# SparkFun_GPS_RTK_Surveyor.net
KiCad netlist of a schematic drawn in EAGLE
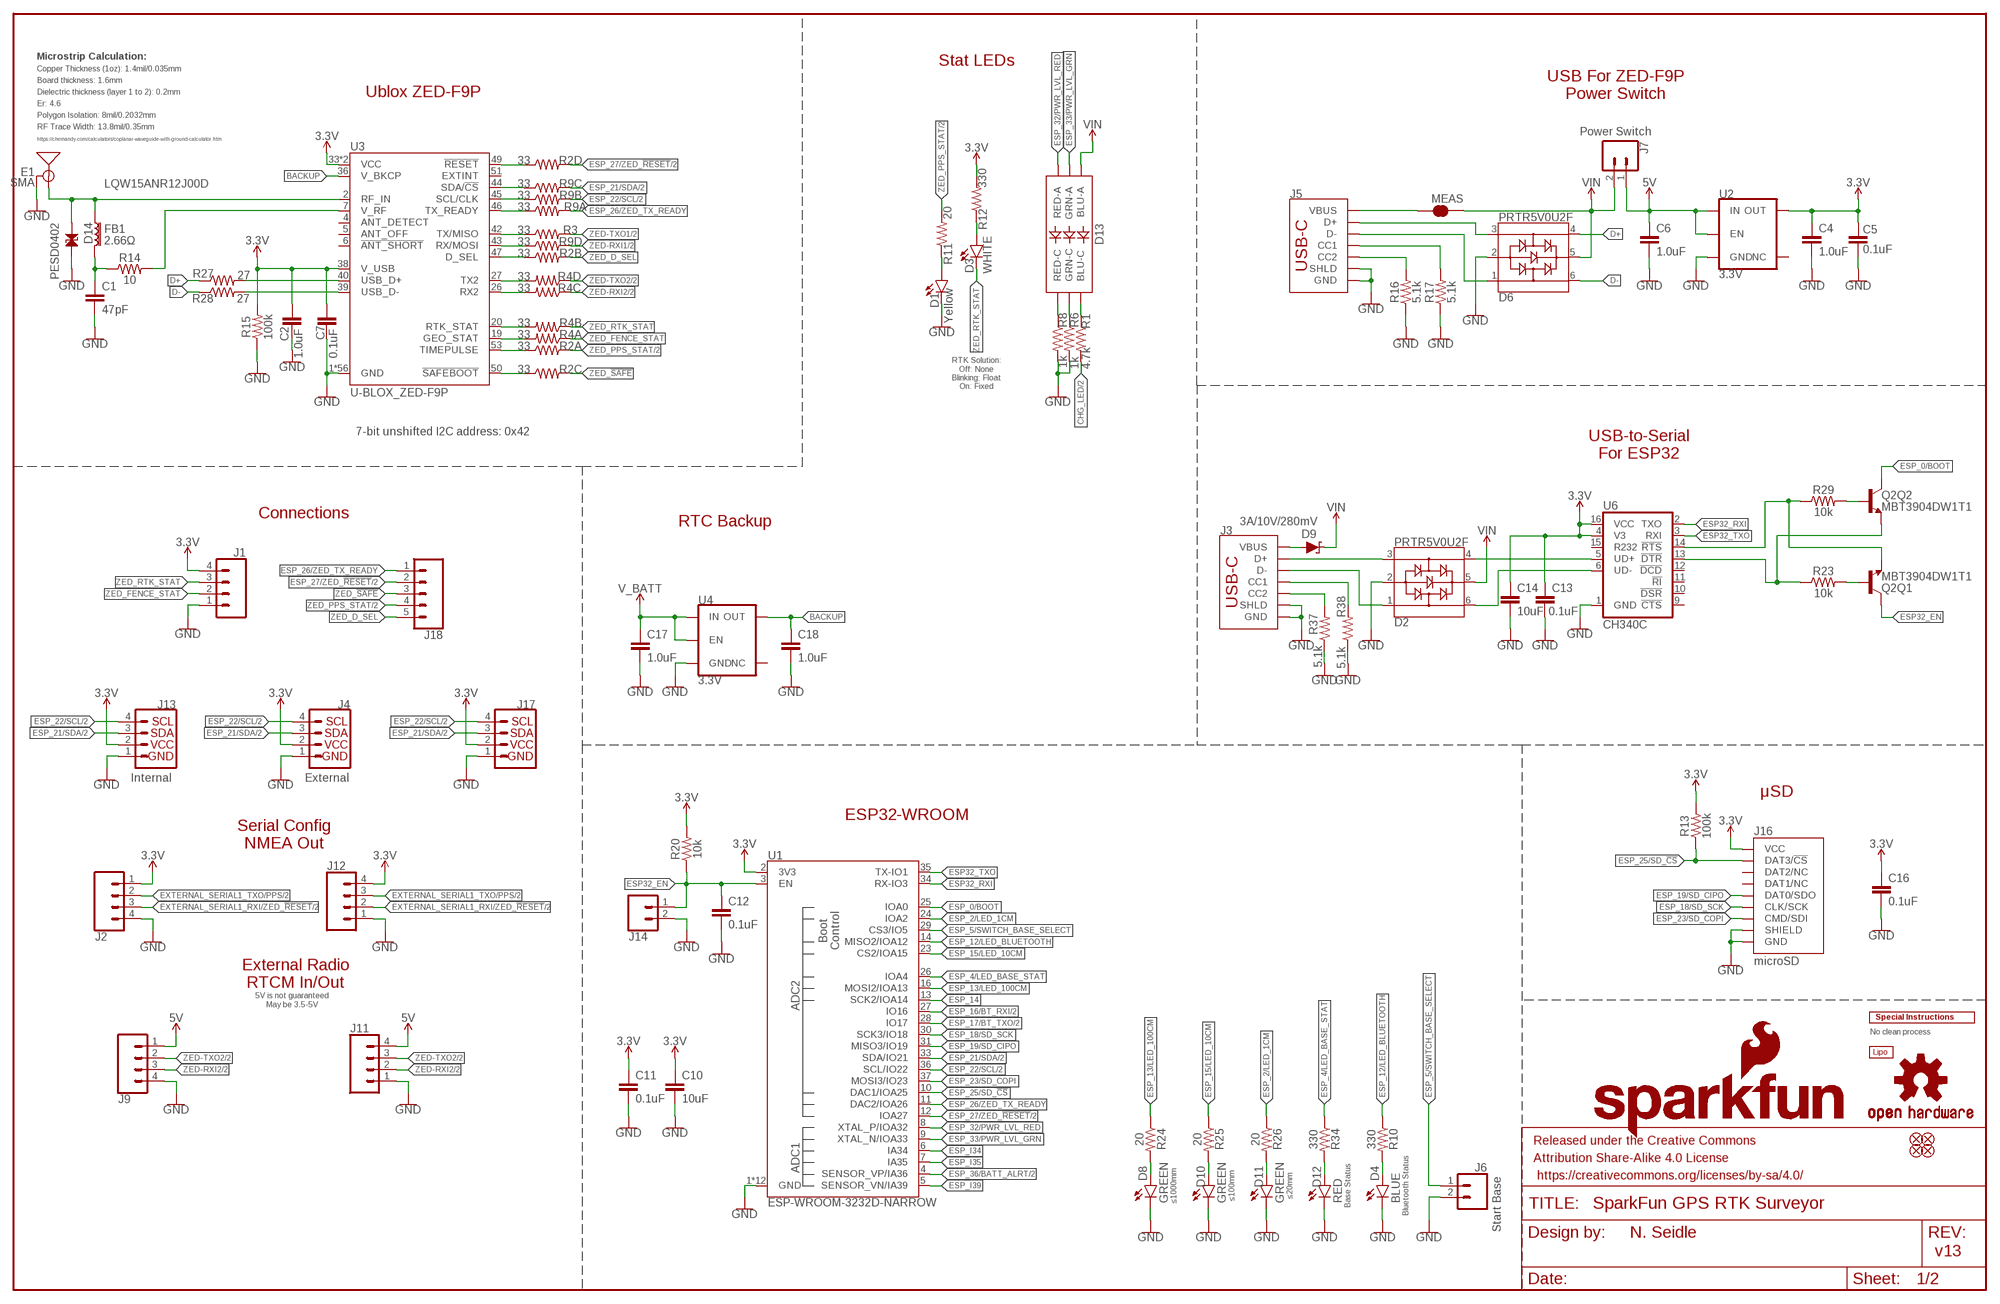
[diagram p0: schematic, sheet 1]
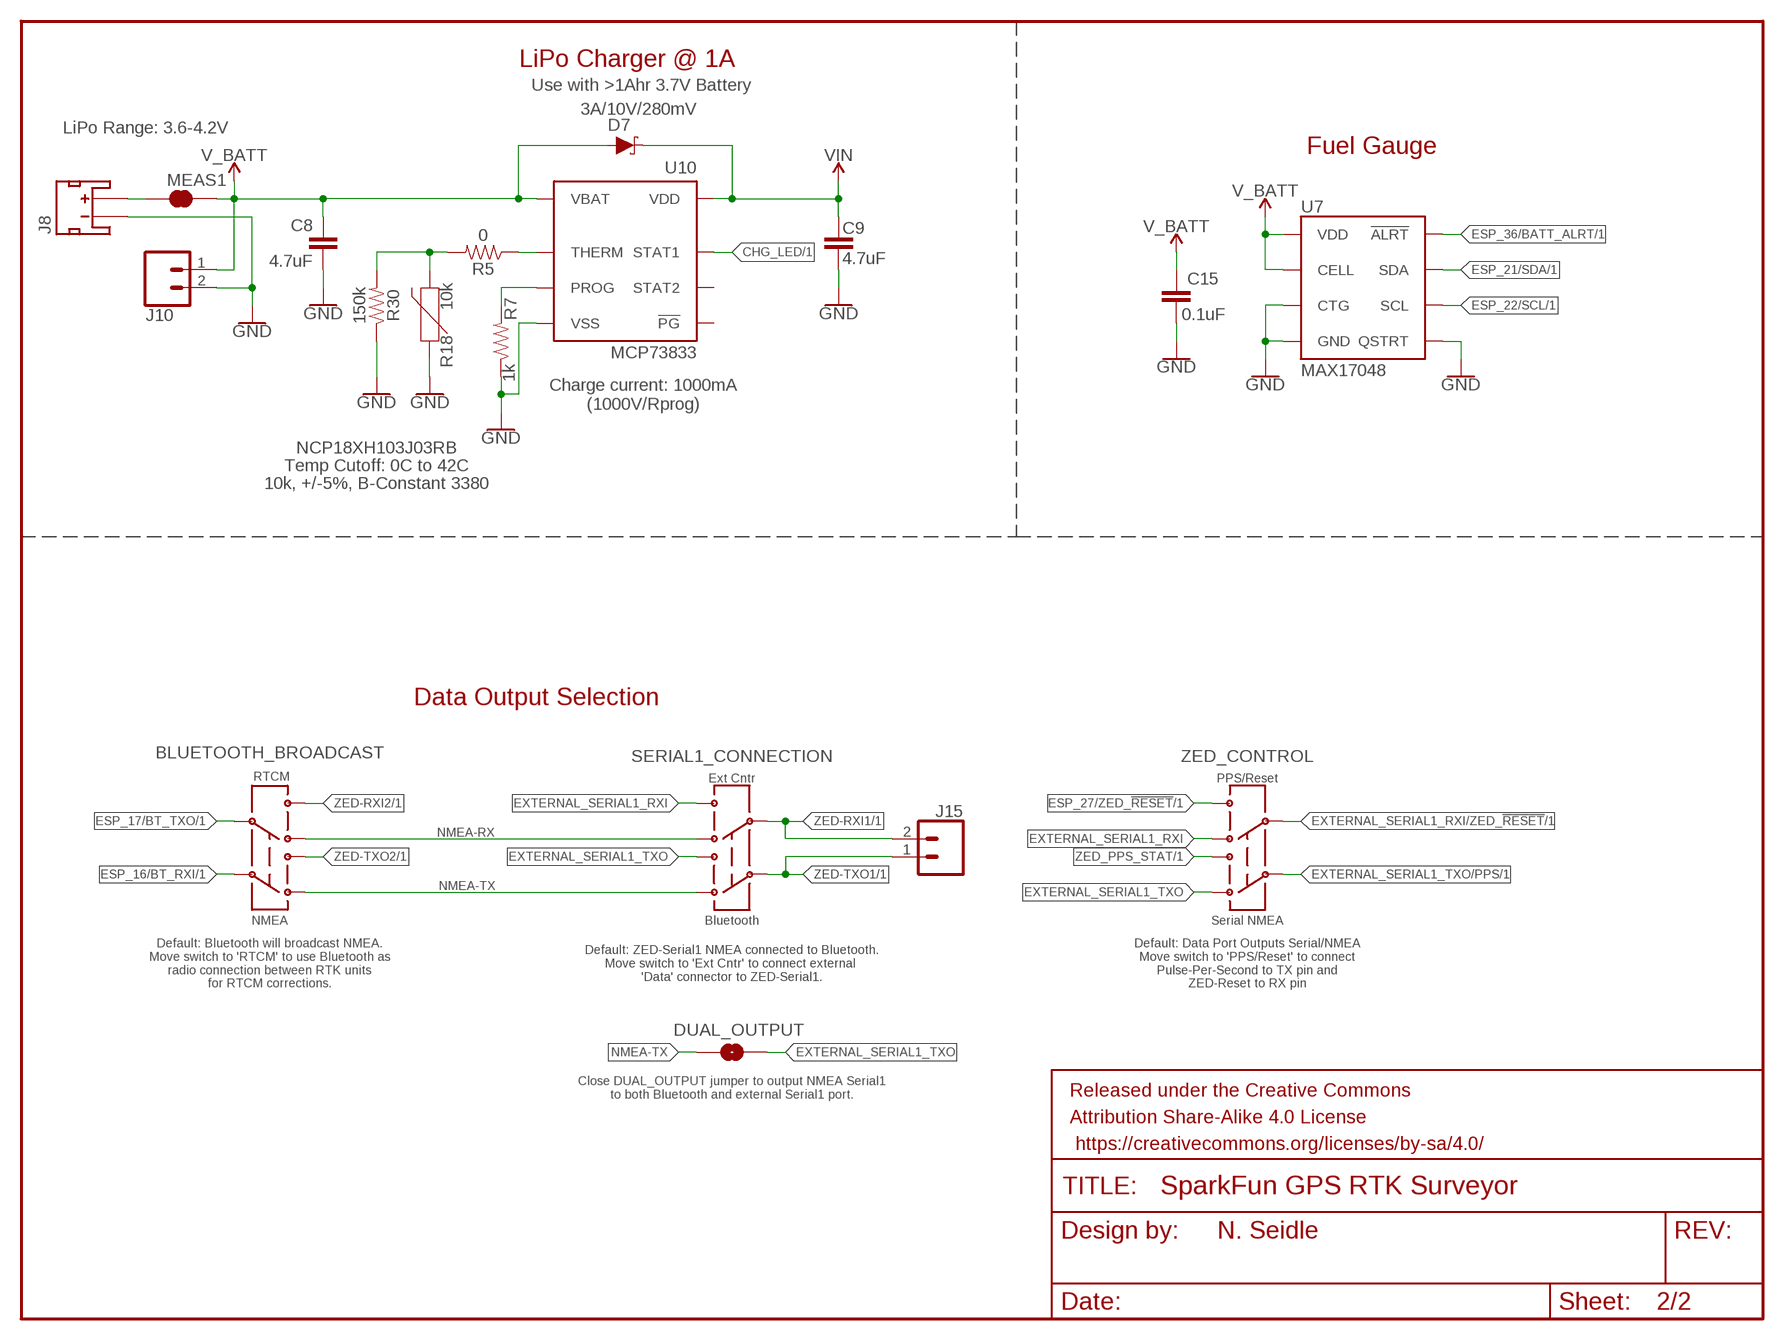
[diagram p1: schematic, sheet 2]

(export (version "E")
  (design (tool "Eeschema 10.0.6"))
  (components
    (comp (ref "BT1")
      (value "LIPO-OUTLINE1000")
      (footprint "eagle-import:LIPO-1000")
      (libsource (lib "eagle-import") (part "LIPO-OUTLINE1000"))
    )
    (comp (ref "C1")
      (value "47pF")
      (footprint "eagle-import:0402")
      (libsource (lib "eagle-import") (part "47PF-0402-25V-5%-X7R"))
    )
    (comp (ref "C2")
      (value "1.0uF")
      (footprint "eagle-import:0603")
      (libsource (lib "eagle-import") (part "1.0UF-0603-16V-10%-X7R"))
    )
    (comp (ref "C4")
      (value "1.0uF")
      (footprint "eagle-import:0603")
      (libsource (lib "eagle-import") (part "1.0UF-0603-16V-10%-X7R"))
    )
    (comp (ref "C5")
      (value "0.1uF")
      (footprint "eagle-import:0603")
      (libsource (lib "eagle-import") (part "0.1UF-0603-25V-5%"))
    )
    (comp (ref "C6")
      (value "1.0uF")
      (footprint "eagle-import:0603")
      (libsource (lib "eagle-import") (part "1.0UF-0603-16V-10%-X7R"))
    )
    (comp (ref "C7")
      (value "0.1uF")
      (footprint "eagle-import:0603")
      (libsource (lib "eagle-import") (part "0.1UF-0603-25V-5%"))
    )
    (comp (ref "C10")
      (value "10uF")
      (footprint "eagle-import:0603")
      (libsource (lib "eagle-import") (part "10UF-0603-6.3V-20%"))
    )
    (comp (ref "C11")
      (value "0.1uF")
      (footprint "eagle-import:0603")
      (libsource (lib "eagle-import") (part "0.1UF-0603-25V-(+80/-20%)"))
    )
    (comp (ref "C12")
      (value "0.1uF")
      (footprint "eagle-import:0603")
      (libsource (lib "eagle-import") (part "0.1UF-0603-25V-(+80/-20%)"))
    )
    (comp (ref "C13")
      (value "0.1uF")
      (footprint "eagle-import:0603")
      (libsource (lib "eagle-import") (part "0.1UF-0603-25V-(+80/-20%)"))
    )
    (comp (ref "C14")
      (value "10uF")
      (footprint "eagle-import:0603")
      (libsource (lib "eagle-import") (part "10UF-0603-6.3V-20%"))
    )
    (comp (ref "C16")
      (value "0.1uF")
      (footprint "eagle-import:0603")
      (libsource (lib "eagle-import") (part "0.1UF-0603-25V-(+80/-20%)"))
    )
    (comp (ref "C17")
      (value "1.0uF")
      (footprint "eagle-import:0603")
      (libsource (lib "eagle-import") (part "1.0UF-0603-16V-10%-X7R"))
    )
    (comp (ref "C18")
      (value "1.0uF")
      (footprint "eagle-import:0603")
      (libsource (lib "eagle-import") (part "1.0UF-0603-16V-10%-X7R"))
    )
    (comp (ref "D1")
      (value "Yellow")
      (footprint "eagle-import:LED-0603")
      (libsource (lib "eagle-import") (part "LED-YELLOW0603"))
    )
    (comp (ref "D2")
      (value "PRTR5V0U2F")
      (footprint "eagle-import:SOT886")
      (libsource (lib "eagle-import") (part "PRTR5V0U2F"))
    )
    (comp (ref "D3")
      (value "WHITE")
      (footprint "eagle-import:LED-0603")
      (libsource (lib "eagle-import") (part "LED-WHITE0603"))
    )
    (comp (ref "D4")
      (value "BLUE")
      (footprint "eagle-import:LED-0603")
      (libsource (lib "eagle-import") (part "LED-BLUE0603"))
    )
    (comp (ref "D6")
      (value "PRTR5V0U2F")
      (footprint "eagle-import:SOT886")
      (libsource (lib "eagle-import") (part "PRTR5V0U2F"))
    )
    (comp (ref "D8")
      (value "GREEN")
      (footprint "eagle-import:LED-0603")
      (libsource (lib "eagle-import") (part "LED-GREEN0603"))
    )
    (comp (ref "D9")
      (value "3A/10V/280mV")
      (footprint "eagle-import:SOD-323")
      (libsource (lib "eagle-import") (part "DIODE-SCHOTTKY-BAT60A"))
    )
    (comp (ref "D10")
      (value "GREEN")
      (footprint "eagle-import:LED-0603")
      (libsource (lib "eagle-import") (part "LED-GREEN0603"))
    )
    (comp (ref "D11")
      (value "GREEN")
      (footprint "eagle-import:LED-0603")
      (libsource (lib "eagle-import") (part "LED-GREEN0603"))
    )
    (comp (ref "D12")
      (value "RED")
      (footprint "eagle-import:LED-0603")
      (libsource (lib "eagle-import") (part "LED-RED0603"))
    )
    (comp (ref "D13")
      (value "LED-RGBBRG")
      (footprint "eagle-import:LED-TRICOLOR-5050")
      (libsource (lib "eagle-import") (part "LED-RGBBRG"))
    )
    (comp (ref "D14")
      (value "PESD0402")
      (footprint "eagle-import:0402")
      (fields
        (field (name "DIGIKEY_PART") "PESD0402-140CT-ND")
        (field (name "MOUSE_PART") "650-PESD0402-140")
      )
      (libsource (lib "eagle-import") (part "PESD0402"))
    )
    (comp (ref "E1")
      (value "SMA")
      (footprint "eagle-import:SMA-EDGE-SMD")
      (libsource (lib "eagle-import") (part "ANTENNA-SMA-GROUNDEDEDGE_SMA_SMD"))
    )
    (comp (ref "FB1")
      (value "2.66Ω")
      (footprint "eagle-import:0402-TIGHT")
      (libsource (lib "eagle-import") (part "FERRITE_BEAD-0402-2.66Ω-1GHZ"))
    )
    (comp (ref "FRAME2")
      (value "FRAME-LEDGER")
      (footprint "eagle-import:CREATIVE_COMMONS")
      (libsource (lib "eagle-import") (part "FRAME-LEDGER"))
    )
    (comp (ref "J1")
      (value "CONN_041X04_NO_SILK_NO_POP")
      (footprint "eagle-import:1X04_NO_SILK")
      (libsource (lib "eagle-import") (part "CONN_041X04_NO_SILK_NO_POP"))
    )
    (comp (ref "J2")
      (value "CONN_04JST-SMD-LOCKING")
      (footprint "eagle-import:JST-4-SMD-1.25MM-LOCKING")
      (libsource (lib "eagle-import") (part "CONN_04JST-SMD-LOCKING"))
    )
    (comp (ref "J3")
      (value "USB Female Type C Connector")
      (footprint "eagle-import:USB-C-16P_4LAYER-PADS")
      (libsource (lib "eagle-import") (part "USB_C_4-LAYER_PADS"))
    )
    (comp (ref "J4")
      (value "External")
      (footprint "eagle-import:JST04_1MM_RA")
      (libsource (lib "eagle-import") (part "I2C_STANDARDQWIIC"))
    )
    (comp (ref "J5")
      (value "USB Female Type C Connector")
      (footprint "eagle-import:USB-C-16P_4LAYER-PADS")
      (libsource (lib "eagle-import") (part "USB_C_4-LAYER_PADS"))
    )
    (comp (ref "J6")
      (value "Start Base")
      (footprint "eagle-import:JST-2-SMD")
      (libsource (lib "eagle-import") (part "CONN_02-JST-2MM-SMT"))
    )
    (comp (ref "J7")
      (value "Power Switch")
      (footprint "eagle-import:JST-2-SMD")
      (libsource (lib "eagle-import") (part "CONN_02-JST-2MM-SMT"))
    )
    (comp (ref "J9")
      (value "CONN_04JST-SMD-LOCKING")
      (footprint "eagle-import:JST-4-SMD-1.25MM-LOCKING")
      (libsource (lib "eagle-import") (part "CONN_04JST-SMD-LOCKING"))
    )
    (comp (ref "J11")
      (value "CONN_041X04_NO_SILK_NO_POP")
      (footprint "eagle-import:1X04_NO_SILK")
      (libsource (lib "eagle-import") (part "CONN_041X04_NO_SILK_NO_POP"))
    )
    (comp (ref "J12")
      (value "CONN_041X04_NO_SILK_NO_POP")
      (footprint "eagle-import:1X04_NO_SILK")
      (libsource (lib "eagle-import") (part "CONN_041X04_NO_SILK_NO_POP"))
    )
    (comp (ref "J13")
      (value "Internal")
      (footprint "eagle-import:JST04_1MM_RA")
      (libsource (lib "eagle-import") (part "I2C_STANDARDQWIIC"))
    )
    (comp (ref "J14")
      (value "CONN_021X02_NO_SILK")
      (footprint "eagle-import:1X02_NO_SILK")
      (libsource (lib "eagle-import") (part "CONN_021X02_NO_SILK"))
    )
    (comp (ref "J16")
      (value "microSD")
      (footprint "eagle-import:MICRO-SD-SOCKET")
      (libsource (lib "eagle-import") (part "MICRO-SD-SDIOPUSH-PUSH"))
    )
    (comp (ref "J17")
      (value "Qwiic Right Angle")
      (footprint "eagle-import:1X04_NO_SILK")
      (libsource (lib "eagle-import") (part "I2C_STANDARD_NO_SILK"))
    )
    (comp (ref "J18")
      (value "CONN_05NO_SILK")
      (footprint "eagle-import:1X05_NO_SILK")
      (libsource (lib "eagle-import") (part "CONN_05NO_SILK"))
    )
    (comp (ref "JP21")
      (value "FIDUCIALUFIDUCIAL")
      (footprint "eagle-import:FIDUCIAL-MICRO")
      (libsource (lib "eagle-import") (part "FIDUCIALUFIDUCIAL"))
    )
    (comp (ref "JP61")
      (value "FIDUCIALUFIDUCIAL")
      (footprint "eagle-import:FIDUCIAL-MICRO")
      (libsource (lib "eagle-import") (part "FIDUCIALUFIDUCIAL"))
    )
    (comp (ref "JP71")
      (value "FIDUCIALUFIDUCIAL")
      (footprint "eagle-import:FIDUCIAL-MICRO")
      (libsource (lib "eagle-import") (part "FIDUCIALUFIDUCIAL"))
    )
    (comp (ref "JP81")
      (value "FIDUCIALUFIDUCIAL")
      (footprint "eagle-import:FIDUCIAL-MICRO")
      (libsource (lib "eagle-import") (part "FIDUCIALUFIDUCIAL"))
    )
    (comp (ref "LOGO1")
      (value "OSHW-LOGOMINI")
      (footprint "eagle-import:OSHW-LOGO-MINI")
      (libsource (lib "eagle-import") (part "OSHW-LOGOMINI"))
    )
    (comp (ref "LOGO2")
      (value "SFE_LOGO_NAME_FLAME.1_INCH")
      (footprint "eagle-import:SFE_LOGO_NAME_FLAME_.1")
      (libsource (lib "eagle-import") (part "SFE_LOGO_NAME_FLAME.1_INCH"))
    )
    (comp (ref "MEAS")
      (value "JUMPER-COMBO_2_NC_TRACE")
      (footprint "eagle-import:COMBO-JUMPER_2_NC_TRACE")
      (libsource (lib "eagle-import") (part "JUMPER-COMBO_2_NC_TRACE"))
    )
    (comp (ref "Q2")
      (value "MBT3904DW1T1")
      (footprint "eagle-import:SC70-6")
      (libsource (lib "eagle-import") (part "TRANS_NPN_DUAL-MBT3904DW1T1"))
    )
    (comp (ref "R1")
      (value "4.7k")
      (footprint "eagle-import:0603")
      (libsource (lib "eagle-import") (part "4.7KOHM-0603-1/10W-1%"))
    )
    (comp (ref "R2")
      (value "33")
      (footprint "eagle-import:1206_RA")
      (libsource (lib "eagle-import") (part "33OHM_RA-1206-1/16W-5%"))
    )
    (comp (ref "R3")
      (value "33")
      (footprint "eagle-import:0603")
      (libsource (lib "eagle-import") (part "33OHM-0603-1/10W-1%"))
    )
    (comp (ref "R4")
      (value "33")
      (footprint "eagle-import:1206_RA")
      (libsource (lib "eagle-import") (part "33OHM_RA-1206-1/16W-5%"))
    )
    (comp (ref "R6")
      (value "1k")
      (footprint "eagle-import:0603")
      (libsource (lib "eagle-import") (part "1KOHM-0603-1/10W-1%"))
    )
    (comp (ref "R8")
      (value "1k")
      (footprint "eagle-import:0603")
      (libsource (lib "eagle-import") (part "1KOHM-0603-1/10W-1%"))
    )
    (comp (ref "R9")
      (value "33")
      (footprint "eagle-import:1206_RA")
      (libsource (lib "eagle-import") (part "33OHM_RA-1206-1/16W-5%"))
    )
    (comp (ref "R10")
      (value "330")
      (footprint "eagle-import:0603")
      (libsource (lib "eagle-import") (part "330OHM-0603-1/10W-1%"))
    )
    (comp (ref "R11")
      (value "20")
      (footprint "eagle-import:0603")
      (libsource (lib "eagle-import") (part "20OHM-0603-1/10W-1%"))
    )
    (comp (ref "R12")
      (value "330")
      (footprint "eagle-import:0603")
      (libsource (lib "eagle-import") (part "330OHM-0603-1/10W-1%"))
    )
    (comp (ref "R13")
      (value "100k")
      (footprint "eagle-import:0603")
      (libsource (lib "eagle-import") (part "100KOHM-0603-1/10W-1%"))
    )
    (comp (ref "R14")
      (value "10")
      (footprint "eagle-import:0603")
      (libsource (lib "eagle-import") (part "10OHM-0603-1/10W-1%"))
    )
    (comp (ref "R15")
      (value "100k")
      (footprint "eagle-import:0603")
      (libsource (lib "eagle-import") (part "100KOHM-0603-1/10W-1%"))
    )
    (comp (ref "R16")
      (value "5.1k")
      (footprint "eagle-import:0603")
      (libsource (lib "eagle-import") (part "5.1KOHM5.1KOHM-0603-1/10W-1%"))
    )
    (comp (ref "R17")
      (value "5.1k")
      (footprint "eagle-import:0603")
      (libsource (lib "eagle-import") (part "5.1KOHM5.1KOHM-0603-1/10W-1%"))
    )
    (comp (ref "R20")
      (value "10k")
      (footprint "eagle-import:0603")
      (libsource (lib "eagle-import") (part "10KOHM-0603-1/10W-1%"))
    )
    (comp (ref "R23")
      (value "10k")
      (footprint "eagle-import:0603")
      (libsource (lib "eagle-import") (part "10KOHM-0603-1/10W-1%"))
    )
    (comp (ref "R24")
      (value "20")
      (footprint "eagle-import:0603")
      (libsource (lib "eagle-import") (part "20OHM-0603-1/10W-1%"))
    )
    (comp (ref "R25")
      (value "20")
      (footprint "eagle-import:0603")
      (libsource (lib "eagle-import") (part "20OHM-0603-1/10W-1%"))
    )
    (comp (ref "R26")
      (value "20")
      (footprint "eagle-import:0603")
      (libsource (lib "eagle-import") (part "20OHM-0603-1/10W-1%"))
    )
    (comp (ref "R27")
      (value "27")
      (footprint "eagle-import:0603")
      (libsource (lib "eagle-import") (part "27OHM-0603-1/10W-1%"))
    )
    (comp (ref "R28")
      (value "27")
      (footprint "eagle-import:0603")
      (libsource (lib "eagle-import") (part "27OHM-0603-1/10W-1%"))
    )
    (comp (ref "R29")
      (value "10k")
      (footprint "eagle-import:0603")
      (libsource (lib "eagle-import") (part "10KOHM-0603-1/10W-1%"))
    )
    (comp (ref "R34")
      (value "330")
      (footprint "eagle-import:0603")
      (libsource (lib "eagle-import") (part "330OHM-0603-1/10W-1%"))
    )
    (comp (ref "R37")
      (value "5.1k")
      (footprint "eagle-import:0603")
      (libsource (lib "eagle-import") (part "5.1KOHM5.1KOHM-0603-1/10W-1%"))
    )
    (comp (ref "R38")
      (value "5.1k")
      (footprint "eagle-import:0603")
      (libsource (lib "eagle-import") (part "5.1KOHM5.1KOHM-0603-1/10W-1%"))
    )
    (comp (ref "U$2")
      (value "SPECIAL_INSTRUCTIONS-ORDERING")
      (footprint "eagle-import:ORDERING_INSTRUCTIONS")
      (libsource (lib "eagle-import") (part "SPECIAL_INSTRUCTIONS-ORDERING"))
    )
    (comp (ref "U1")
      (value "ESP-WROOM-3232D-NARROW")
      (footprint "eagle-import:ESP-WROOM-32D-NARROW")
      (libsource (lib "eagle-import") (part "ESP-WROOM-3232D-NARROW"))
    )
    (comp (ref "U2")
      (value "3.3V")
      (footprint "eagle-import:SOT23-5")
      (libsource (lib "eagle-import") (part "V_REG_AP2112K-3.3V"))
    )
    (comp (ref "U3")
      (value "U-BLOX_ZED-F9P")
      (footprint "eagle-import:ZED-F9P")
      (libsource (lib "eagle-import") (part "U-BLOX_ZED-F9P"))
    )
    (comp (ref "U4")
      (value "3.3V")
      (footprint "eagle-import:SOT23-5")
      (libsource (lib "eagle-import") (part "V_REG_AP2112K-3.3V"))
    )
    (comp (ref "U6")
      (value "CH340C")
      (footprint "eagle-import:SO016")
      (libsource (lib "eagle-import") (part "CH340C"))
    )
    (comp (ref "BLUETOOTH_BROADCAST")
      (value "SWITCH-DPDT-SMD-AYZ0202")
      (footprint "eagle-import:SWITCH_DPDT_SMD_AYZ0202")
      (libsource (lib "eagle-import") (part "SWITCH-DPDT-SMD-AYZ0202"))
    )
    (comp (ref "C8")
      (value "4.7uF")
      (footprint "eagle-import:0603")
      (libsource (lib "eagle-import") (part "4.7UF-0603-35V-(20%)"))
    )
    (comp (ref "C9")
      (value "4.7uF")
      (footprint "eagle-import:0603")
      (libsource (lib "eagle-import") (part "4.7UF-0603-35V-(20%)"))
    )
    (comp (ref "C15")
      (value "0.1uF")
      (footprint "eagle-import:0603")
      (libsource (lib "eagle-import") (part "0.1UF-0603-25V-(+80/-20%)"))
    )
    (comp (ref "D7")
      (value "3A/10V/280mV")
      (footprint "eagle-import:SOD-323")
      (libsource (lib "eagle-import") (part "DIODE-SCHOTTKY-BAT60A"))
    )
    (comp (ref "DUAL_OUTPUT")
      (value "JUMPER-SMT_2_NO_SILK")
      (footprint "eagle-import:SMT-JUMPER_2_NO_SILK")
      (libsource (lib "eagle-import") (part "JUMPER-SMT_2_NO_SILK"))
    )
    (comp (ref "FRAME1")
      (value "FRAME-LETTERNO_PACKAGE")
      (footprint "eagle-import:DUMMY")
      (fields (field (name "DESIGNER") "Nobody"))
      (libsource (lib "eagle-import") (part "FRAME-LETTERNO_PACKAGE"))
    )
    (comp (ref "J8")
      (value "JST_2MM_MALE")
      (footprint "eagle-import:JST-2-SMD")
      (libsource (lib "eagle-import") (part "JST_2MM_MALE"))
    )
    (comp (ref "J10")
      (value "CONN_021X02_NO_SILK")
      (footprint "eagle-import:1X02_NO_SILK")
      (libsource (lib "eagle-import") (part "CONN_021X02_NO_SILK"))
    )
    (comp (ref "J15")
      (value "CONN_021X02_NO_SILK")
      (footprint "eagle-import:1X02_NO_SILK")
      (libsource (lib "eagle-import") (part "CONN_021X02_NO_SILK"))
    )
    (comp (ref "MEAS1")
      (value "JUMPER-COMBO_2_NC_TRACE")
      (footprint "eagle-import:COMBO-JUMPER_2_NC_TRACE")
      (libsource (lib "eagle-import") (part "JUMPER-COMBO_2_NC_TRACE"))
    )
    (comp (ref "R5")
      (value "0")
      (footprint "eagle-import:0603")
      (libsource (lib "eagle-import") (part "0OHM-0603-1/10W"))
    )
    (comp (ref "R7")
      (value "1k")
      (footprint "eagle-import:0603")
      (libsource (lib "eagle-import") (part "1KOHM-0603-1/10W-1%"))
    )
    (comp (ref "R18")
      (value "10k")
      (footprint "eagle-import:0603")
      (libsource (lib "eagle-import") (part "NTC-THERMISTOR-0603"))
    )
    (comp (ref "R30")
      (value "150k")
      (footprint "eagle-import:0603")
      (libsource (lib "eagle-import") (part "150KOHM-0603-1/10W-1%"))
    )
    (comp (ref "SERIAL1_CONNECTION")
      (value "SWITCH-DPDT-SMD-AYZ0202")
      (footprint "eagle-import:SWITCH_DPDT_SMD_AYZ0202")
      (libsource (lib "eagle-import") (part "SWITCH-DPDT-SMD-AYZ0202"))
    )
    (comp (ref "U7")
      (value "MAX17048")
      (footprint "eagle-import:DFN-8")
      (libsource (lib "eagle-import") (part "MAX17048DFN8"))
    )
    (comp (ref "U10")
      (value "MCP73833")
      (footprint "eagle-import:DFN-10")
      (libsource (lib "eagle-import") (part "MCP73833"))
    )
    (comp (ref "ZED_CONTROL")
      (value "SWITCH-DPDT-SMD-AYZ0202")
      (footprint "eagle-import:SWITCH_DPDT_SMD_AYZ0202")
      (libsource (lib "eagle-import") (part "SWITCH-DPDT-SMD-AYZ0202"))
    )
  )
  (nets
    (net (code "1") (name "3.3V") (class "Default")
      (node (ref "C10") (pin "1") (pinfunction "1_1") (pintype "passive"))
      (node (ref "C11") (pin "1") (pinfunction "1_1") (pintype "passive"))
      (node (ref "C13") (pin "1") (pinfunction "1_1") (pintype "passive"))
      (node (ref "C14") (pin "1") (pinfunction "1_1") (pintype "passive"))
      (node (ref "C16") (pin "1") (pinfunction "1_1") (pintype "passive"))
      (node (ref "C2") (pin "1") (pinfunction "1_1") (pintype "passive"))
      (node (ref "C4") (pin "1") (pinfunction "1_1") (pintype "passive"))
      (node (ref "C5") (pin "2") (pinfunction "2_2") (pintype "passive"))
      (node (ref "C7") (pin "2") (pinfunction "2_2") (pintype "passive"))
      (node (ref "J1") (pin "4") (pinfunction "4_4") (pintype "passive"))
      (node (ref "J12") (pin "4") (pinfunction "4_4") (pintype "passive"))
      (node (ref "J13") (pin "2") (pinfunction "2_2") (pintype "power_in"))
      (node (ref "J16") (pin "VCC") (pinfunction "VCC_VCC") (pintype "bidirectional"))
      (node (ref "J17") (pin "2") (pinfunction "2_2") (pintype "power_in"))
      (node (ref "J2") (pin "1") (pinfunction "1_1") (pintype "passive"))
      (node (ref "J4") (pin "2") (pinfunction "2_2") (pintype "power_in"))
      (node (ref "R12") (pin "2") (pinfunction "2_2") (pintype "passive"))
      (node (ref "R13") (pin "2") (pinfunction "2_2") (pintype "passive"))
      (node (ref "R15") (pin "2") (pinfunction "2_2") (pintype "passive"))
      (node (ref "R20") (pin "2") (pinfunction "2_2") (pintype "passive"))
      (node (ref "U1") (pin "2") (pinfunction "3V3_2") (pintype "bidirectional"))
      (node (ref "U2") (pin "5") (pinfunction "OUT_5") (pintype "passive"))
      (node (ref "U3") (pin "33") (pinfunction "VCC_33") (pintype "bidirectional"))
      (node (ref "U3") (pin "34") (pinfunction "VCC_34") (pintype "bidirectional"))
      (node (ref "U3") (pin "38") (pinfunction "V_USB_38") (pintype "bidirectional"))
      (node (ref "U6") (pin "16") (pinfunction "VCC_16") (pintype "bidirectional"))
      (node (ref "U6") (pin "4") (pinfunction "V3_4") (pintype "bidirectional"))
    )
    (net (code "2") (name "5V") (class "Default")
      (node (ref "C6") (pin "1") (pinfunction "1_1") (pintype "passive"))
      (node (ref "J11") (pin "4") (pinfunction "4_4") (pintype "passive"))
      (node (ref "J7") (pin "1") (pinfunction "2_1") (pintype "passive"))
      (node (ref "J9") (pin "1") (pinfunction "1_1") (pintype "passive"))
      (node (ref "U2") (pin "1") (pinfunction "IN_1") (pintype "input"))
      (node (ref "U2") (pin "3") (pinfunction "EN_3") (pintype "input"))
    )
    (net (code "3") (name "BACKUP") (class "Default")
      (node (ref "C18") (pin "1") (pinfunction "1_1") (pintype "passive"))
      (node (ref "U3") (pin "36") (pinfunction "V_BKCP_36") (pintype "bidirectional"))
      (node (ref "U4") (pin "5") (pinfunction "OUT_5") (pintype "passive"))
    )
    (net (code "4") (name "CHG_LED") (class "Default")
      (node (ref "R1") (pin "2") (pinfunction "2_2") (pintype "passive"))
      (node (ref "U10") (pin "3") (pinfunction "STAT1_3") (pintype "bidirectional"))
    )
    (net (code "5") (name "D+") (class "Default")
      (node (ref "D6") (pin "4") (pinfunction "4_4") (pintype "bidirectional"))
      (node (ref "R27") (pin "1") (pinfunction "1_1") (pintype "passive"))
    )
    (net (code "6") (name "D-") (class "Default")
      (node (ref "D6") (pin "6") (pinfunction "6_6") (pintype "bidirectional"))
      (node (ref "R28") (pin "1") (pinfunction "1_1") (pintype "passive"))
    )
    (net (code "7") (name "ESP32_EN") (class "Default")
      (node (ref "C12") (pin "1") (pinfunction "1_1") (pintype "passive"))
      (node (ref "J14") (pin "1") (pinfunction "1_1") (pintype "passive"))
      (node (ref "Q2") (pin "3") (pinfunction "C_3") (pintype "passive"))
      (node (ref "R20") (pin "1") (pinfunction "1_1") (pintype "passive"))
      (node (ref "U1") (pin "3") (pinfunction "EN_3") (pintype "bidirectional"))
    )
    (net (code "8") (name "ESP32_RXI") (class "Default")
      (node (ref "U1") (pin "34") (pinfunction "RX-IO3_34") (pintype "bidirectional"))
      (node (ref "U6") (pin "2") (pinfunction "TXO_2") (pintype "bidirectional"))
    )
    (net (code "9") (name "ESP32_TXO") (class "Default")
      (node (ref "U1") (pin "35") (pinfunction "TX-IO1_35") (pintype "bidirectional"))
      (node (ref "U6") (pin "3") (pinfunction "RXI_3") (pintype "bidirectional"))
    )
    (net (code "10") (name "ESP_0{slash}BOOT") (class "Default")
      (node (ref "Q2") (pin "6") (pinfunction "C_6") (pintype "passive"))
      (node (ref "U1") (pin "25") (pinfunction "IOA0_25") (pintype "bidirectional"))
    )
    (net (code "11") (name "ESP_2{slash}LED_1CM") (class "Default")
      (node (ref "R26") (pin "1") (pinfunction "1_1") (pintype "passive"))
      (node (ref "U1") (pin "24") (pinfunction "IOA2_24") (pintype "bidirectional"))
    )
    (net (code "12") (name "ESP_4{slash}LED_BASE_STAT") (class "Default")
      (node (ref "R34") (pin "1") (pinfunction "1_1") (pintype "passive"))
      (node (ref "U1") (pin "26") (pinfunction "IOA4_26") (pintype "bidirectional"))
    )
    (net (code "13") (name "ESP_5{slash}SWITCH_BASE_SELECT") (class "Default")
      (node (ref "J6") (pin "1") (pinfunction "2_1") (pintype "passive"))
      (node (ref "U1") (pin "29") (pinfunction "CS3/IO5_29") (pintype "bidirectional"))
    )
    (net (code "14") (name "ESP_12{slash}LED_BLUETOOTH") (class "Default")
      (node (ref "R10") (pin "1") (pinfunction "1_1") (pintype "passive"))
      (node (ref "U1") (pin "14") (pinfunction "MISO2/IOA12_14") (pintype "bidirectional"))
    )
    (net (code "15") (name "ESP_13{slash}LED_100CM") (class "Default")
      (node (ref "R24") (pin "1") (pinfunction "1_1") (pintype "passive"))
      (node (ref "U1") (pin "16") (pinfunction "MOSI2/IOA13_16") (pintype "bidirectional"))
    )
    (net (code "16") (name "ESP_14") (class "Default")
      (node (ref "U1") (pin "13") (pinfunction "SCK2/IOA14_13") (pintype "bidirectional"))
    )
    (net (code "17") (name "ESP_15{slash}LED_10CM") (class "Default")
      (node (ref "R25") (pin "1") (pinfunction "1_1") (pintype "passive"))
      (node (ref "U1") (pin "23") (pinfunction "CS2/IOA15_23") (pintype "bidirectional"))
    )
    (net (code "18") (name "ESP_16{slash}BT_RXI") (class "Default")
      (node (ref "BLUETOOTH_BROADCAST") (pin "2") (pinfunction "2_2") (pintype "bidirectional"))
      (node (ref "U1") (pin "27") (pinfunction "IO16_27") (pintype "bidirectional"))
    )
    (net (code "19") (name "ESP_17{slash}BT_TXO") (class "Default")
      (node (ref "BLUETOOTH_BROADCAST") (pin "5") (pinfunction "5_5") (pintype "bidirectional"))
      (node (ref "U1") (pin "28") (pinfunction "IO17_28") (pintype "bidirectional"))
    )
    (net (code "20") (name "ESP_18{slash}SD_SCK") (class "Default")
      (node (ref "J16") (pin "SCLK") (pinfunction "CLK/SCK_SCLK") (pintype "bidirectional"))
      (node (ref "U1") (pin "30") (pinfunction "SCK3/IO18_30") (pintype "bidirectional"))
    )
    (net (code "21") (name "ESP_19{slash}SD_CIPO") (class "Default")
      (node (ref "J16") (pin "DO/DAT0") (pinfunction "DAT0/SDO_DO/DAT0") (pintype "bidirectional"))
      (node (ref "U1") (pin "31") (pinfunction "MISO3/IO19_31") (pintype "bidirectional"))
    )
    (net (code "22") (name "ESP_21{slash}SDA") (class "Default")
      (node (ref "J13") (pin "3") (pinfunction "3_3") (pintype "passive"))
      (node (ref "J17") (pin "3") (pinfunction "3_3") (pintype "passive"))
      (node (ref "J4") (pin "3") (pinfunction "3_3") (pintype "passive"))
      (node (ref "R9") (pin "P6") (pinfunction "2_P6") (pintype "passive"))
      (node (ref "U1") (pin "33") (pinfunction "SDA/IO21_33") (pintype "bidirectional"))
      (node (ref "U7") (pin "8") (pinfunction "SDA_8") (pintype "input"))
    )
    (net (code "23") (name "ESP_22{slash}SCL") (class "Default")
      (node (ref "J13") (pin "4") (pinfunction "4_4") (pintype "passive"))
      (node (ref "J17") (pin "4") (pinfunction "4_4") (pintype "passive"))
      (node (ref "J4") (pin "4") (pinfunction "4_4") (pintype "passive"))
      (node (ref "R9") (pin "P7") (pinfunction "2_P7") (pintype "passive"))
      (node (ref "U1") (pin "36") (pinfunction "SCL/IO22_36") (pintype "bidirectional"))
      (node (ref "U7") (pin "7") (pinfunction "SCL_7") (pintype "output"))
    )
    (net (code "24") (name "ESP_23{slash}SD_COPI") (class "Default")
      (node (ref "J16") (pin "DI/CMD") (pinfunction "CMD/SDI_DI/CMD") (pintype "bidirectional"))
      (node (ref "U1") (pin "37") (pinfunction "MOSI3/IO23_37") (pintype "bidirectional"))
    )
    (net (code "25") (name "ESP_25{slash}SD_~{CS}") (class "Default")
      (node (ref "J16") (pin "CS/DAT3") (pinfunction "DAT3/~{CS}_CS/DAT3") (pintype "bidirectional"))
      (node (ref "R13") (pin "1") (pinfunction "1_1") (pintype "passive"))
      (node (ref "U1") (pin "10") (pinfunction "DAC1/IOA25_10") (pintype "bidirectional"))
    )
    (net (code "26") (name "ESP_26{slash}ZED_TX_READY") (class "Default")
      (node (ref "J18") (pin "1") (pinfunction "1_1") (pintype "passive"))
      (node (ref "R9") (pin "P8") (pinfunction "2_P8") (pintype "passive"))
      (node (ref "U1") (pin "11") (pinfunction "DAC2/IOA26_11") (pintype "bidirectional"))
    )
    (net (code "27") (name "ESP_27{slash}ZED_~{RESET}") (class "Default")
      (node (ref "J18") (pin "2") (pinfunction "2_2") (pintype "passive"))
      (node (ref "R2") (pin "P5") (pinfunction "2_P5") (pintype "passive"))
      (node (ref "U1") (pin "12") (pinfunction "IOA27_12") (pintype "bidirectional"))
      (node (ref "ZED_CONTROL") (pin "4") (pinfunction "4_4") (pintype "bidirectional"))
    )
    (net (code "28") (name "ESP_32{slash}PWR_LVL_RED") (class "Default")
      (node (ref "D13") (pin "5") (pinfunction "RED-A_5") (pintype "bidirectional"))
      (node (ref "U1") (pin "8") (pinfunction "XTAL_P/IOA32_8") (pintype "bidirectional"))
    )
    (net (code "29") (name "ESP_33{slash}PWR_LVL_GRN") (class "Default")
      (node (ref "D13") (pin "4") (pinfunction "GRN-A_4") (pintype "bidirectional"))
      (node (ref "U1") (pin "9") (pinfunction "XTAL_N/IOA33_9") (pintype "bidirectional"))
    )
    (net (code "30") (name "ESP_36{slash}BATT_ALRT") (class "Default")
      (node (ref "U1") (pin "4") (pinfunction "SENSOR_VP/IA36_4") (pintype "bidirectional"))
      (node (ref "U7") (pin "5") (pinfunction "~{ALRT}_5") (pintype "bidirectional"))
    )
    (net (code "31") (name "ESP_I34") (class "Default")
      (node (ref "U1") (pin "6") (pinfunction "IA34_6") (pintype "bidirectional"))
    )
    (net (code "32") (name "ESP_I35") (class "Default")
      (node (ref "U1") (pin "7") (pinfunction "IA35_7") (pintype "bidirectional"))
    )
    (net (code "33") (name "ESP_I39") (class "Default")
      (node (ref "U1") (pin "5") (pinfunction "SENSOR_VN/IA39_5") (pintype "bidirectional"))
    )
    (net (code "34") (name "EXTERNAL_SERIAL1_RXI") (class "Default")
      (node (ref "SERIAL1_CONNECTION") (pin "4") (pinfunction "4_4") (pintype "bidirectional"))
      (node (ref "ZED_CONTROL") (pin "6") (pinfunction "6_6") (pintype "bidirectional"))
    )
    (net (code "35") (name "EXTERNAL_SERIAL1_RXI{slash}ZED_~{RESET}") (class "Default")
      (node (ref "J12") (pin "2") (pinfunction "2_2") (pintype "passive"))
      (node (ref "J2") (pin "3") (pinfunction "3_3") (pintype "passive"))
      (node (ref "ZED_CONTROL") (pin "5") (pinfunction "5_5") (pintype "bidirectional"))
    )
    (net (code "36") (name "EXTERNAL_SERIAL1_TXO") (class "Default")
      (node (ref "DUAL_OUTPUT") (pin "2") (pinfunction "2_2") (pintype "passive"))
      (node (ref "SERIAL1_CONNECTION") (pin "1") (pinfunction "1_1") (pintype "bidirectional"))
      (node (ref "ZED_CONTROL") (pin "3") (pinfunction "3_3") (pintype "bidirectional"))
    )
    (net (code "37") (name "EXTERNAL_SERIAL1_TXO{slash}PPS") (class "Default")
      (node (ref "J12") (pin "3") (pinfunction "3_3") (pintype "passive"))
      (node (ref "J2") (pin "2") (pinfunction "2_2") (pintype "passive"))
      (node (ref "ZED_CONTROL") (pin "2") (pinfunction "2_2") (pintype "bidirectional"))
    )
    (net (code "38") (name "GND") (class "Default")
      (node (ref "C1") (pin "2") (pinfunction "2_2") (pintype "passive"))
      (node (ref "C10") (pin "2") (pinfunction "2_2") (pintype "passive"))
      (node (ref "C11") (pin "2") (pinfunction "2_2") (pintype "passive"))
      (node (ref "C12") (pin "2") (pinfunction "2_2") (pintype "passive"))
      (node (ref "C13") (pin "2") (pinfunction "2_2") (pintype "passive"))
      (node (ref "C14") (pin "2") (pinfunction "2_2") (pintype "passive"))
      (node (ref "C15") (pin "2") (pinfunction "2_2") (pintype "passive"))
      (node (ref "C16") (pin "2") (pinfunction "2_2") (pintype "passive"))
      (node (ref "C17") (pin "2") (pinfunction "2_2") (pintype "passive"))
      (node (ref "C18") (pin "2") (pinfunction "2_2") (pintype "passive"))
      (node (ref "C2") (pin "2") (pinfunction "2_2") (pintype "passive"))
      (node (ref "C4") (pin "2") (pinfunction "2_2") (pintype "passive"))
      (node (ref "C5") (pin "1") (pinfunction "1_1") (pintype "passive"))
      (node (ref "C6") (pin "2") (pinfunction "2_2") (pintype "passive"))
      (node (ref "C7") (pin "1") (pinfunction "1_1") (pintype "passive"))
      (node (ref "C8") (pin "2") (pinfunction "2_2") (pintype "passive"))
      (node (ref "C9") (pin "2") (pinfunction "2_2") (pintype "passive"))
      (node (ref "D1") (pin "C") (pinfunction "C_C") (pintype "passive"))
      (node (ref "D10") (pin "C") (pinfunction "C_C") (pintype "passive"))
      (node (ref "D11") (pin "C") (pinfunction "C_C") (pintype "passive"))
      (node (ref "D12") (pin "C") (pinfunction "C_C") (pintype "passive"))
      (node (ref "D14") (pin "2") (pinfunction "2_2") (pintype "bidirectional"))
      (node (ref "D2") (pin "2") (pinfunction "2_2") (pintype "power_in"))
      (node (ref "D4") (pin "C") (pinfunction "C_C") (pintype "passive"))
      (node (ref "D6") (pin "2") (pinfunction "2_2") (pintype "power_in"))
      (node (ref "D8") (pin "C") (pinfunction "C_C") (pintype "passive"))
      (node (ref "E1") (pin "GND@0") (pinfunction "GND_GND@0") (pintype "bidirectional"))
      (node (ref "E1") (pin "GND@1") (pinfunction "GND_GND@1") (pintype "bidirectional"))
      (node (ref "J1") (pin "1") (pinfunction "1_1") (pintype "passive"))
      (node (ref "J10") (pin "2") (pinfunction "2_2") (pintype "passive"))
      (node (ref "J11") (pin "1") (pinfunction "1_1") (pintype "passive"))
      (node (ref "J12") (pin "1") (pinfunction "1_1") (pintype "passive"))
      (node (ref "J13") (pin "1") (pinfunction "1_1") (pintype "power_in"))
      (node (ref "J14") (pin "2") (pinfunction "2_2") (pintype "passive"))
      (node (ref "J16") (pin "CD1") (pinfunction "SHIELD_CD1") (pintype "bidirectional"))
      (node (ref "J16") (pin "GND") (pinfunction "GND_GND") (pintype "bidirectional"))
      (node (ref "J16") (pin "GND1") (pinfunction "GND_GND1") (pintype "bidirectional"))
      (node (ref "J16") (pin "GND3") (pinfunction "GND_GND3") (pintype "bidirectional"))
      (node (ref "J17") (pin "1") (pinfunction "1_1") (pintype "power_in"))
      (node (ref "J2") (pin "4") (pinfunction "4_4") (pintype "passive"))
      (node (ref "J3") (pin "GND") (pinfunction "GND_GND") (pintype "bidirectional"))
      (node (ref "J3") (pin "GND2") (pinfunction "GND_GND2") (pintype "bidirectional"))
      (node (ref "J3") (pin "SHLD1") (pinfunction "SHLD_SHLD1") (pintype "bidirectional"))
      (node (ref "J3") (pin "SHLD2") (pinfunction "SHLD_SHLD2") (pintype "bidirectional"))
      (node (ref "J3") (pin "SHLD3") (pinfunction "SHLD_SHLD3") (pintype "bidirectional"))
      (node (ref "J3") (pin "SHLD4") (pinfunction "SHLD_SHLD4") (pintype "bidirectional"))
      (node (ref "J4") (pin "1") (pinfunction "1_1") (pintype "power_in"))
      (node (ref "J5") (pin "GND") (pinfunction "GND_GND") (pintype "bidirectional"))
      (node (ref "J5") (pin "GND2") (pinfunction "GND_GND2") (pintype "bidirectional"))
      (node (ref "J5") (pin "SHLD1") (pinfunction "SHLD_SHLD1") (pintype "bidirectional"))
      (node (ref "J5") (pin "SHLD2") (pinfunction "SHLD_SHLD2") (pintype "bidirectional"))
      (node (ref "J5") (pin "SHLD3") (pinfunction "SHLD_SHLD3") (pintype "bidirectional"))
      (node (ref "J5") (pin "SHLD4") (pinfunction "SHLD_SHLD4") (pintype "bidirectional"))
      (node (ref "J6") (pin "2") (pinfunction "1_2") (pintype "passive"))
      (node (ref "J8") (pin "1") (pinfunction "-_1") (pintype "bidirectional"))
      (node (ref "J9") (pin "4") (pinfunction "4_4") (pintype "passive"))
      (node (ref "R15") (pin "1") (pinfunction "1_1") (pintype "passive"))
      (node (ref "R16") (pin "1") (pinfunction "1_1") (pintype "passive"))
      (node (ref "R17") (pin "1") (pinfunction "1_1") (pintype "passive"))
      (node (ref "R18") (pin "1") (pinfunction "1_1") (pintype "bidirectional"))
      (node (ref "R30") (pin "1") (pinfunction "1_1") (pintype "passive"))
      (node (ref "R37") (pin "1") (pinfunction "1_1") (pintype "passive"))
      (node (ref "R38") (pin "1") (pinfunction "1_1") (pintype "passive"))
      (node (ref "R6") (pin "2") (pinfunction "2_2") (pintype "passive"))
      (node (ref "R7") (pin "1") (pinfunction "1_1") (pintype "passive"))
      (node (ref "R8") (pin "2") (pinfunction "2_2") (pintype "passive"))
      (node (ref "U1") (pin "1") (pinfunction "GND_1") (pintype "bidirectional"))
      (node (ref "U1") (pin "15") (pinfunction "GND_15") (pintype "bidirectional"))
      (node (ref "U1") (pin "38") (pinfunction "GND_38") (pintype "bidirectional"))
      (node (ref "U1") (pin "GND1") (pinfunction "GND_GND1") (pintype "bidirectional"))
      (node (ref "U1") (pin "GNDT1") (pinfunction "GND_GNDT1") (pintype "bidirectional"))
      (node (ref "U1") (pin "GNDT2") (pinfunction "GND_GNDT2") (pintype "bidirectional"))
      (node (ref "U1") (pin "GNDT3") (pinfunction "GND_GNDT3") (pintype "bidirectional"))
      (node (ref "U1") (pin "GNDT4") (pinfunction "GND_GNDT4") (pintype "bidirectional"))
      (node (ref "U1") (pin "GNDT5") (pinfunction "GND_GNDT5") (pintype "bidirectional"))
      (node (ref "U1") (pin "GNDT6") (pinfunction "GND_GNDT6") (pintype "bidirectional"))
      (node (ref "U1") (pin "GNDT7") (pinfunction "GND_GNDT7") (pintype "bidirectional"))
      (node (ref "U1") (pin "GNDT8") (pinfunction "GND_GNDT8") (pintype "bidirectional"))
      (node (ref "U10") (pin "11") (pinfunction "VSS_11") (pintype "bidirectional"))
      (node (ref "U10") (pin "5") (pinfunction "VSS_5") (pintype "bidirectional"))
      (node (ref "U2") (pin "2") (pinfunction "GND_2") (pintype "input"))
      (node (ref "U3") (pin "1") (pinfunction "GND_1") (pintype "bidirectional"))
      (node (ref "U3") (pin "100") (pinfunction "GND_100") (pintype "bidirectional"))
      (node (ref "U3") (pin "101") (pinfunction "GND_101") (pintype "bidirectional"))
      (node (ref "U3") (pin "102") (pinfunction "GND_102") (pintype "bidirectional"))
      (node (ref "U3") (pin "12") (pinfunction "GND_12") (pintype "bidirectional"))
      (node (ref "U3") (pin "14") (pinfunction "GND_14") (pintype "bidirectional"))
      (node (ref "U3") (pin "3") (pinfunction "GND_3") (pintype "bidirectional"))
      (node (ref "U3") (pin "32") (pinfunction "GND_32") (pintype "bidirectional"))
      (node (ref "U3") (pin "37") (pinfunction "GND_37") (pintype "bidirectional"))
      (node (ref "U3") (pin "41") (pinfunction "GND_41") (pintype "bidirectional"))
      (node (ref "U3") (pin "48") (pinfunction "GND_48") (pintype "bidirectional"))
      (node (ref "U3") (pin "55") (pinfunction "GND_55") (pintype "bidirectional"))
      (node (ref "U3") (pin "56") (pinfunction "GND_56") (pintype "bidirectional"))
      (node (ref "U3") (pin "57") (pinfunction "GND_57") (pintype "bidirectional"))
      (node (ref "U3") (pin "58") (pinfunction "GND_58") (pintype "bidirectional"))
      (node (ref "U3") (pin "59") (pinfunction "GND_59") (pintype "bidirectional"))
      (node (ref "U3") (pin "60") (pinfunction "GND_60") (pintype "bidirectional"))
      (node (ref "U3") (pin "61") (pinfunction "GND_61") (pintype "bidirectional"))
      (node (ref "U3") (pin "62") (pinfunction "GND_62") (pintype "bidirectional"))
      (node (ref "U3") (pin "63") (pinfunction "GND_63") (pintype "bidirectional"))
      (node (ref "U3") (pin "64") (pinfunction "GND_64") (pintype "bidirectional"))
      (node (ref "U3") (pin "65") (pinfunction "GND_65") (pintype "bidirectional"))
      (node (ref "U3") (pin "66") (pinfunction "GND_66") (pintype "bidirectional"))
      (node (ref "U3") (pin "67") (pinfunction "GND_67") (pintype "bidirectional"))
      (node (ref "U3") (pin "68") (pinfunction "GND_68") (pintype "bidirectional"))
      (node (ref "U3") (pin "69") (pinfunction "GND_69") (pintype "bidirectional"))
      (node (ref "U3") (pin "70") (pinfunction "GND_70") (pintype "bidirectional"))
      (node (ref "U3") (pin "71") (pinfunction "GND_71") (pintype "bidirectional"))
      (node (ref "U3") (pin "72") (pinfunction "GND_72") (pintype "bidirectional"))
      (node (ref "U3") (pin "73") (pinfunction "GND_73") (pintype "bidirectional"))
      (node (ref "U3") (pin "74") (pinfunction "GND_74") (pintype "bidirectional"))
      (node (ref "U3") (pin "75") (pinfunction "GND_75") (pintype "bidirectional"))
      (node (ref "U3") (pin "76") (pinfunction "GND_76") (pintype "bidirectional"))
      (node (ref "U3") (pin "77") (pinfunction "GND_77") (pintype "bidirectional"))
      (node (ref "U3") (pin "78") (pinfunction "GND_78") (pintype "bidirectional"))
      (node (ref "U3") (pin "79") (pinfunction "GND_79") (pintype "bidirectional"))
      (node (ref "U3") (pin "80") (pinfunction "GND_80") (pintype "bidirectional"))
      (node (ref "U3") (pin "81") (pinfunction "GND_81") (pintype "bidirectional"))
      (node (ref "U3") (pin "82") (pinfunction "GND_82") (pintype "bidirectional"))
      (node (ref "U3") (pin "83") (pinfunction "GND_83") (pintype "bidirectional"))
      (node (ref "U3") (pin "84") (pinfunction "GND_84") (pintype "bidirectional"))
      (node (ref "U3") (pin "85") (pinfunction "GND_85") (pintype "bidirectional"))
      (node (ref "U3") (pin "86") (pinfunction "GND_86") (pintype "bidirectional"))
      (node (ref "U3") (pin "87") (pinfunction "GND_87") (pintype "bidirectional"))
      (node (ref "U3") (pin "88") (pinfunction "GND_88") (pintype "bidirectional"))
      (node (ref "U3") (pin "89") (pinfunction "GND_89") (pintype "bidirectional"))
      (node (ref "U3") (pin "90") (pinfunction "GND_90") (pintype "bidirectional"))
      (node (ref "U3") (pin "91") (pinfunction "GND_91") (pintype "bidirectional"))
      (node (ref "U3") (pin "92") (pinfunction "GND_92") (pintype "bidirectional"))
      (node (ref "U3") (pin "93") (pinfunction "GND_93") (pintype "bidirectional"))
      (node (ref "U3") (pin "94") (pinfunction "GND_94") (pintype "bidirectional"))
      (node (ref "U3") (pin "95") (pinfunction "GND_95") (pintype "bidirectional"))
      (node (ref "U3") (pin "96") (pinfunction "GND_96") (pintype "bidirectional"))
      (node (ref "U3") (pin "97") (pinfunction "GND_97") (pintype "bidirectional"))
      (node (ref "U3") (pin "98") (pinfunction "GND_98") (pintype "bidirectional"))
      (node (ref "U3") (pin "99") (pinfunction "GND_99") (pintype "bidirectional"))
      (node (ref "U4") (pin "2") (pinfunction "GND_2") (pintype "input"))
      (node (ref "U6") (pin "1") (pinfunction "GND_1") (pintype "bidirectional"))
      (node (ref "U7") (pin "1") (pinfunction "CTG_1") (pintype "input"))
      (node (ref "U7") (pin "4") (pinfunction "GND_4") (pintype "bidirectional"))
      (node (ref "U7") (pin "6") (pinfunction "QSTRT_6") (pintype "bidirectional"))
      (node (ref "U7") (pin "9") (pinfunction "GND_9") (pintype "bidirectional"))
    )
    (net (code "39") (name "NMEA-RX") (class "Default")
      (node (ref "BLUETOOTH_BROADCAST") (pin "6") (pinfunction "6_6") (pintype "bidirectional"))
      (node (ref "SERIAL1_CONNECTION") (pin "6") (pinfunction "6_6") (pintype "bidirectional"))
    )
    (net (code "40") (name "NMEA-TX") (class "Default")
      (node (ref "BLUETOOTH_BROADCAST") (pin "3") (pinfunction "3_3") (pintype "bidirectional"))
      (node (ref "DUAL_OUTPUT") (pin "1") (pinfunction "1_1") (pintype "passive"))
      (node (ref "SERIAL1_CONNECTION") (pin "3") (pinfunction "3_3") (pintype "bidirectional"))
    )
    (net (code "41") (name "Net-(C1-Pad1)") (class "Default")
      (node (ref "C1") (pin "1") (pinfunction "1_1") (pintype "passive"))
      (node (ref "FB1") (pin "2") (pinfunction "2_2") (pintype "passive"))
      (node (ref "R14") (pin "1") (pinfunction "1_1") (pintype "passive"))
    )
    (net (code "42") (name "Net-(D1-PadA)") (class "Default")
      (node (ref "D1") (pin "A") (pinfunction "A_A") (pintype "passive"))
      (node (ref "R11") (pin "1") (pinfunction "1_1") (pintype "passive"))
    )
    (net (code "43") (name "Net-(D2-Pad1)") (class "Default")
      (node (ref "D2") (pin "1") (pinfunction "1_1") (pintype "bidirectional"))
      (node (ref "J3") (pin "A7") (pinfunction "D-_A7") (pintype "bidirectional"))
      (node (ref "J3") (pin "B7") (pinfunction "D-_B7") (pintype "bidirectional"))
    )
    (net (code "44") (name "Net-(D2-Pad3)") (class "Default")
      (node (ref "D2") (pin "3") (pinfunction "3_3") (pintype "bidirectional"))
      (node (ref "J3") (pin "A6") (pinfunction "D+_A6") (pintype "bidirectional"))
      (node (ref "J3") (pin "B6") (pinfunction "D+_B6") (pintype "bidirectional"))
    )
    (net (code "45") (name "Net-(D3-PadA)") (class "Default")
      (node (ref "D3") (pin "A") (pinfunction "A_A") (pintype "passive"))
      (node (ref "R12") (pin "1") (pinfunction "1_1") (pintype "passive"))
    )
    (net (code "46") (name "Net-(D4-PadA)") (class "Default")
      (node (ref "D4") (pin "A") (pinfunction "A_A") (pintype "passive"))
      (node (ref "R10") (pin "2") (pinfunction "2_2") (pintype "passive"))
    )
    (net (code "47") (name "Net-(D6-Pad1)") (class "Default")
      (node (ref "D6") (pin "1") (pinfunction "1_1") (pintype "bidirectional"))
      (node (ref "J5") (pin "A7") (pinfunction "D-_A7") (pintype "bidirectional"))
      (node (ref "J5") (pin "B7") (pinfunction "D-_B7") (pintype "bidirectional"))
    )
    (net (code "48") (name "Net-(D6-Pad3)") (class "Default")
      (node (ref "D6") (pin "3") (pinfunction "3_3") (pintype "bidirectional"))
      (node (ref "J5") (pin "A6") (pinfunction "D+_A6") (pintype "bidirectional"))
      (node (ref "J5") (pin "B6") (pinfunction "D+_B6") (pintype "bidirectional"))
    )
    (net (code "49") (name "Net-(D8-PadA)") (class "Default")
      (node (ref "D8") (pin "A") (pinfunction "A_A") (pintype "passive"))
      (node (ref "R24") (pin "2") (pinfunction "2_2") (pintype "passive"))
    )
    (net (code "50") (name "Net-(D9-PadA)") (class "Default")
      (node (ref "D9") (pin "A") (pinfunction "A_A") (pintype "passive"))
      (node (ref "J3") (pin "VBUS1") (pinfunction "VBUS_VBUS1") (pintype "bidirectional"))
      (node (ref "J3") (pin "VBUS2") (pinfunction "VBUS_VBUS2") (pintype "bidirectional"))
    )
    (net (code "51") (name "Net-(D10-PadA)") (class "Default")
      (node (ref "D10") (pin "A") (pinfunction "A_A") (pintype "passive"))
      (node (ref "R25") (pin "2") (pinfunction "2_2") (pintype "passive"))
    )
    (net (code "52") (name "Net-(D11-PadA)") (class "Default")
      (node (ref "D11") (pin "A") (pinfunction "A_A") (pintype "passive"))
      (node (ref "R26") (pin "2") (pinfunction "2_2") (pintype "passive"))
    )
    (net (code "53") (name "Net-(D12-PadA)") (class "Default")
      (node (ref "D12") (pin "A") (pinfunction "A_A") (pintype "passive"))
      (node (ref "R34") (pin "2") (pinfunction "2_2") (pintype "passive"))
    )
    (net (code "54") (name "Net-(D13-BLU-C)") (class "Default")
      (node (ref "D13") (pin "1") (pinfunction "BLU-C_1") (pintype "bidirectional"))
      (node (ref "R1") (pin "1") (pinfunction "1_1") (pintype "passive"))
    )
    (net (code "55") (name "Net-(D13-GRN-C)") (class "Default")
      (node (ref "D13") (pin "3") (pinfunction "GRN-C_3") (pintype "bidirectional"))
      (node (ref "R6") (pin "1") (pinfunction "1_1") (pintype "passive"))
    )
    (net (code "56") (name "Net-(D13-RED-C)") (class "Default")
      (node (ref "D13") (pin "2") (pinfunction "RED-C_2") (pintype "bidirectional"))
      (node (ref "R8") (pin "1") (pinfunction "1_1") (pintype "passive"))
    )
    (net (code "57") (name "Net-(E1-SIGNAL)") (class "Default")
      (node (ref "D14") (pin "1") (pinfunction "1_1") (pintype "bidirectional"))
      (node (ref "E1") (pin "SIG") (pinfunction "SIGNAL_SIG") (pintype "bidirectional"))
      (node (ref "FB1") (pin "1") (pinfunction "1_1") (pintype "passive"))
      (node (ref "U3") (pin "2") (pinfunction "RF_IN_2") (pintype "bidirectional"))
    )
    (net (code "58") (name "Net-(J3-CC1)") (class "Default")
      (node (ref "J3") (pin "A5") (pinfunction "CC1_A5") (pintype "bidirectional"))
      (node (ref "R38") (pin "2") (pinfunction "2_2") (pintype "passive"))
    )
    (net (code "59") (name "Net-(J3-CC2)") (class "Default")
      (node (ref "J3") (pin "B5") (pinfunction "CC2_B5") (pintype "bidirectional"))
      (node (ref "R37") (pin "2") (pinfunction "2_2") (pintype "passive"))
    )
    (net (code "60") (name "Net-(J5-CC1)") (class "Default")
      (node (ref "J5") (pin "A5") (pinfunction "CC1_A5") (pintype "bidirectional"))
      (node (ref "R17") (pin "2") (pinfunction "2_2") (pintype "passive"))
    )
    (net (code "61") (name "Net-(J5-CC2)") (class "Default")
      (node (ref "J5") (pin "B5") (pinfunction "CC2_B5") (pintype "bidirectional"))
      (node (ref "R16") (pin "2") (pinfunction "2_2") (pintype "passive"))
    )
    (net (code "62") (name "Net-(J5-VBUS-PadVBUS1)") (class "Default")
      (node (ref "J5") (pin "VBUS1") (pinfunction "VBUS_VBUS1") (pintype "bidirectional"))
      (node (ref "J5") (pin "VBUS2") (pinfunction "VBUS_VBUS2") (pintype "bidirectional"))
      (node (ref "MEAS") (pin "1") (pinfunction "1_1") (pintype "passive"))
      (node (ref "MEAS") (pin "3") (pinfunction "1_3") (pintype "passive"))
    )
    (net (code "63") (name "Net-(J8-+)") (class "Default")
      (node (ref "J8") (pin "2") (pinfunction "+_2") (pintype "bidirectional"))
      (node (ref "MEAS1") (pin "1") (pinfunction "1_1") (pintype "passive"))
      (node (ref "MEAS1") (pin "3") (pinfunction "1_3") (pintype "passive"))
    )
    (net (code "64") (name "Net-(Q2A-B)") (class "Default")
      (node (ref "Q2") (pin "5") (pinfunction "B_5") (pintype "passive"))
      (node (ref "R23") (pin "2") (pinfunction "2_2") (pintype "passive"))
    )
    (net (code "65") (name "Net-(Q2A-E)") (class "Default")
      (node (ref "Q2") (pin "4") (pinfunction "E_4") (pintype "passive"))
      (node (ref "R29") (pin "1") (pinfunction "1_1") (pintype "passive"))
      (node (ref "U6") (pin "14") (pinfunction "~{RTS}_14") (pintype "bidirectional"))
    )
    (net (code "66") (name "Net-(Q2B-B)") (class "Default")
      (node (ref "Q2") (pin "2") (pinfunction "B_2") (pintype "passive"))
      (node (ref "R29") (pin "2") (pinfunction "2_2") (pintype "passive"))
    )
    (net (code "67") (name "Net-(Q2B-E)") (class "Default")
      (node (ref "Q2") (pin "1") (pinfunction "E_1") (pintype "passive"))
      (node (ref "R23") (pin "1") (pinfunction "1_1") (pintype "passive"))
      (node (ref "U6") (pin "13") (pinfunction "~{DTR}_13") (pintype "bidirectional"))
    )
    (net (code "68") (name "Net-(R2A-1)") (class "Default")
      (node (ref "R2") (pin "P1") (pinfunction "1_P1") (pintype "passive"))
      (node (ref "U3") (pin "53") (pinfunction "TIMEPULSE_53") (pintype "bidirectional"))
    )
    (net (code "69") (name "Net-(R2B-1)") (class "Default")
      (node (ref "R2") (pin "P2") (pinfunction "1_P2") (pintype "passive"))
      (node (ref "U3") (pin "47") (pinfunction "D_SEL_47") (pintype "bidirectional"))
    )
    (net (code "70") (name "Net-(R2C-1)") (class "Default")
      (node (ref "R2") (pin "P3") (pinfunction "1_P3") (pintype "passive"))
      (node (ref "U3") (pin "50") (pinfunction "~{SAFEBOOT}_50") (pintype "bidirectional"))
    )
    (net (code "71") (name "Net-(R2D-1)") (class "Default")
      (node (ref "R2") (pin "P4") (pinfunction "1_P4") (pintype "passive"))
      (node (ref "U3") (pin "49") (pinfunction "~{RESET}_49") (pintype "bidirectional"))
    )
    (net (code "72") (name "Net-(R4A-2)") (class "Default")
      (node (ref "R4") (pin "P8") (pinfunction "2_P8") (pintype "passive"))
      (node (ref "U3") (pin "19") (pinfunction "GEO_STAT_19") (pintype "bidirectional"))
    )
    (net (code "73") (name "Net-(R4B-2)") (class "Default")
      (node (ref "R4") (pin "P7") (pinfunction "2_P7") (pintype "passive"))
      (node (ref "U3") (pin "20") (pinfunction "RTK_STAT_20") (pintype "bidirectional"))
    )
    (net (code "74") (name "Net-(R4C-2)") (class "Default")
      (node (ref "R4") (pin "P6") (pinfunction "2_P6") (pintype "passive"))
      (node (ref "U3") (pin "26") (pinfunction "RX2_26") (pintype "bidirectional"))
    )
    (net (code "75") (name "Net-(R4D-2)") (class "Default")
      (node (ref "R4") (pin "P5") (pinfunction "2_P5") (pintype "passive"))
      (node (ref "U3") (pin "27") (pinfunction "TX2_27") (pintype "bidirectional"))
    )
    (net (code "76") (name "Net-(R9A-1)") (class "Default")
      (node (ref "R9") (pin "P1") (pinfunction "1_P1") (pintype "passive"))
      (node (ref "U3") (pin "46") (pinfunction "TX_READY_46") (pintype "bidirectional"))
    )
    (net (code "77") (name "Net-(R9B-1)") (class "Default")
      (node (ref "R9") (pin "P2") (pinfunction "1_P2") (pintype "passive"))
      (node (ref "U3") (pin "45") (pinfunction "SCL/CLK_45") (pintype "bidirectional"))
    )
    (net (code "78") (name "Net-(R9C-1)") (class "Default")
      (node (ref "R9") (pin "P3") (pinfunction "1_P3") (pintype "passive"))
      (node (ref "U3") (pin "44") (pinfunction "SDA/~{CS}_44") (pintype "bidirectional"))
    )
    (net (code "79") (name "Net-(R9D-1)") (class "Default")
      (node (ref "R9") (pin "P4") (pinfunction "1_P4") (pintype "passive"))
      (node (ref "U3") (pin "43") (pinfunction "RX/MOSI_43") (pintype "bidirectional"))
    )
    (net (code "80") (name "Net-(R18-Pad2)") (class "Default")
      (node (ref "R18") (pin "2") (pinfunction "2_2") (pintype "bidirectional"))
      (node (ref "R30") (pin "2") (pinfunction "2_2") (pintype "passive"))
      (node (ref "R5") (pin "2") (pinfunction "2_2") (pintype "passive"))
    )
    (net (code "81") (name "Net-(U3-TX{slash}MISO)") (class "Default")
      (node (ref "R3") (pin "1") (pinfunction "1_1") (pintype "passive"))
      (node (ref "U3") (pin "42") (pinfunction "TX/MISO_42") (pintype "bidirectional"))
    )
    (net (code "82") (name "Net-(U3-USB_D+)") (class "Default")
      (node (ref "R27") (pin "2") (pinfunction "2_2") (pintype "passive"))
      (node (ref "U3") (pin "40") (pinfunction "USB_D+_40") (pintype "bidirectional"))
    )
    (net (code "83") (name "Net-(U3-USB_D-)") (class "Default")
      (node (ref "R28") (pin "2") (pinfunction "2_2") (pintype "passive"))
      (node (ref "U3") (pin "39") (pinfunction "USB_D-_39") (pintype "bidirectional"))
    )
    (net (code "84") (name "Net-(U3-V_RF)") (class "Default")
      (node (ref "R14") (pin "2") (pinfunction "2_2") (pintype "passive"))
      (node (ref "U3") (pin "7") (pinfunction "V_RF_7") (pintype "bidirectional"))
    )
    (net (code "85") (name "Net-(U6-UD+)") (class "Default")
      (node (ref "D2") (pin "4") (pinfunction "4_4") (pintype "bidirectional"))
      (node (ref "U6") (pin "5") (pinfunction "UD+_5") (pintype "bidirectional"))
    )
    (net (code "86") (name "Net-(U6-UD-)") (class "Default")
      (node (ref "D2") (pin "6") (pinfunction "6_6") (pintype "bidirectional"))
      (node (ref "U6") (pin "6") (pinfunction "UD-_6") (pintype "bidirectional"))
    )
    (net (code "87") (name "Net-(U10-PROG)") (class "Default")
      (node (ref "R7") (pin "2") (pinfunction "2_2") (pintype "passive"))
      (node (ref "U10") (pin "6") (pinfunction "PROG_6") (pintype "bidirectional"))
    )
    (net (code "88") (name "Net-(U10-THERM)") (class "Default")
      (node (ref "R5") (pin "1") (pinfunction "1_1") (pintype "passive"))
      (node (ref "U10") (pin "8") (pinfunction "THERM_8") (pintype "bidirectional"))
    )
    (net (code "89") (name "VIN") (class "Default")
      (node (ref "C9") (pin "1") (pinfunction "1_1") (pintype "passive"))
      (node (ref "D13") (pin "6") (pinfunction "BLU-A_6") (pintype "bidirectional"))
      (node (ref "D2") (pin "5") (pinfunction "5_5") (pintype "power_in"))
      (node (ref "D6") (pin "5") (pinfunction "5_5") (pintype "power_in"))
      (node (ref "D7") (pin "C") (pinfunction "C_C") (pintype "passive"))
      (node (ref "D9") (pin "C") (pinfunction "C_C") (pintype "passive"))
      (node (ref "J7") (pin "2") (pinfunction "1_2") (pintype "passive"))
      (node (ref "MEAS") (pin "2") (pinfunction "2_2") (pintype "passive"))
      (node (ref "MEAS") (pin "4") (pinfunction "2_4") (pintype "passive"))
      (node (ref "U10") (pin "1") (pinfunction "VDD_1") (pintype "bidirectional"))
      (node (ref "U10") (pin "2") (pinfunction "VDD_2") (pintype "bidirectional"))
    )
    (net (code "90") (name "V_BATT") (class "Default")
      (node (ref "C15") (pin "1") (pinfunction "1_1") (pintype "passive"))
      (node (ref "C17") (pin "1") (pinfunction "1_1") (pintype "passive"))
      (node (ref "C8") (pin "1") (pinfunction "1_1") (pintype "passive"))
      (node (ref "D7") (pin "A") (pinfunction "A_A") (pintype "passive"))
      (node (ref "J10") (pin "1") (pinfunction "1_1") (pintype "passive"))
      (node (ref "MEAS1") (pin "2") (pinfunction "2_2") (pintype "passive"))
      (node (ref "MEAS1") (pin "4") (pinfunction "2_4") (pintype "passive"))
      (node (ref "U10") (pin "10") (pinfunction "VBAT_10") (pintype "bidirectional"))
      (node (ref "U10") (pin "9") (pinfunction "VBAT_9") (pintype "bidirectional"))
      (node (ref "U4") (pin "1") (pinfunction "IN_1") (pintype "input"))
      (node (ref "U4") (pin "3") (pinfunction "EN_3") (pintype "input"))
      (node (ref "U7") (pin "2") (pinfunction "CELL_2") (pintype "input"))
      (node (ref "U7") (pin "3") (pinfunction "VDD_3") (pintype "bidirectional"))
    )
    (net (code "91") (name "ZED-RXI1") (class "Default")
      (node (ref "J15") (pin "2") (pinfunction "2_2") (pintype "passive"))
      (node (ref "R9") (pin "P5") (pinfunction "2_P5") (pintype "passive"))
      (node (ref "SERIAL1_CONNECTION") (pin "5") (pinfunction "5_5") (pintype "bidirectional"))
    )
    (net (code "92") (name "ZED-RXI2") (class "Default")
      (node (ref "BLUETOOTH_BROADCAST") (pin "4") (pinfunction "4_4") (pintype "bidirectional"))
      (node (ref "J11") (pin "2") (pinfunction "2_2") (pintype "passive"))
      (node (ref "J9") (pin "3") (pinfunction "3_3") (pintype "passive"))
      (node (ref "R4") (pin "P3") (pinfunction "1_P3") (pintype "passive"))
    )
    (net (code "93") (name "ZED-TXO1") (class "Default")
      (node (ref "J15") (pin "1") (pinfunction "1_1") (pintype "passive"))
      (node (ref "R3") (pin "2") (pinfunction "2_2") (pintype "passive"))
      (node (ref "SERIAL1_CONNECTION") (pin "2") (pinfunction "2_2") (pintype "bidirectional"))
    )
    (net (code "94") (name "ZED-TXO2") (class "Default")
      (node (ref "BLUETOOTH_BROADCAST") (pin "1") (pinfunction "1_1") (pintype "bidirectional"))
      (node (ref "J11") (pin "3") (pinfunction "3_3") (pintype "passive"))
      (node (ref "J9") (pin "2") (pinfunction "2_2") (pintype "passive"))
      (node (ref "R4") (pin "P4") (pinfunction "1_P4") (pintype "passive"))
    )
    (net (code "95") (name "ZED_D_SEL") (class "Default")
      (node (ref "J18") (pin "5") (pinfunction "5_5") (pintype "passive"))
      (node (ref "R2") (pin "P7") (pinfunction "2_P7") (pintype "passive"))
    )
    (net (code "96") (name "ZED_FENCE_STAT") (class "Default")
      (node (ref "J1") (pin "2") (pinfunction "2_2") (pintype "passive"))
      (node (ref "R4") (pin "P1") (pinfunction "1_P1") (pintype "passive"))
    )
    (net (code "97") (name "ZED_PPS_STAT") (class "Default")
      (node (ref "J18") (pin "4") (pinfunction "4_4") (pintype "passive"))
      (node (ref "R11") (pin "2") (pinfunction "2_2") (pintype "passive"))
      (node (ref "R2") (pin "P8") (pinfunction "2_P8") (pintype "passive"))
      (node (ref "ZED_CONTROL") (pin "1") (pinfunction "1_1") (pintype "bidirectional"))
    )
    (net (code "98") (name "ZED_RTK_STAT") (class "Default")
      (node (ref "D3") (pin "C") (pinfunction "C_C") (pintype "passive"))
      (node (ref "J1") (pin "3") (pinfunction "3_3") (pintype "passive"))
      (node (ref "R4") (pin "P2") (pinfunction "1_P2") (pintype "passive"))
    )
    (net (code "99") (name "ZED_~{SAFE}") (class "Default")
      (node (ref "J18") (pin "3") (pinfunction "3_3") (pintype "passive"))
      (node (ref "R2") (pin "P6") (pinfunction "2_P6") (pintype "passive"))
    )
    (net (code "100") (name "unconnected-(J8-PAD1-PadNC1)") (class "Default")
      (node (ref "J8") (pin "NC1") (pinfunction "PAD1_NC1") (pintype "bidirectional"))
    )
    (net (code "101") (name "unconnected-(J8-PAD2-PadNC2)") (class "Default")
      (node (ref "J8") (pin "NC2") (pinfunction "PAD2_NC2") (pintype "bidirectional"))
    )
    (net (code "102") (name "unconnected-(J16-DAT1{slash}NC-PadDAT1)") (class "Default")
      (node (ref "J16") (pin "DAT1") (pinfunction "DAT1/NC_DAT1") (pintype "bidirectional"))
    )
    (net (code "103") (name "unconnected-(J16-DAT2{slash}NC-PadDAT2)") (class "Default")
      (node (ref "J16") (pin "DAT2") (pinfunction "DAT2/NC_DAT2") (pintype "bidirectional"))
    )
    (net (code "104") (name "unconnected-(U2-NC-Pad4)") (class "Default")
      (node (ref "U2") (pin "4") (pinfunction "NC_4") (pintype "no_connect"))
    )
    (net (code "105") (name "unconnected-(U3-ANT_DETECT-Pad4)") (class "Default")
      (node (ref "U3") (pin "4") (pinfunction "ANT_DETECT_4") (pintype "bidirectional"))
    )
    (net (code "106") (name "unconnected-(U3-ANT_OFF-Pad5)") (class "Default")
      (node (ref "U3") (pin "5") (pinfunction "ANT_OFF_5") (pintype "bidirectional"))
    )
    (net (code "107") (name "unconnected-(U3-EXTINT-Pad51)") (class "Default")
      (node (ref "U3") (pin "51") (pinfunction "EXTINT_51") (pintype "bidirectional"))
    )
    (net (code "108") (name "unconnected-(U3-~{ANT_SHORT}-Pad6)") (class "Default")
      (node (ref "U3") (pin "6") (pinfunction "~{ANT_SHORT}_6") (pintype "bidirectional"))
    )
    (net (code "109") (name "unconnected-(U4-NC-Pad4)") (class "Default")
      (node (ref "U4") (pin "4") (pinfunction "NC_4") (pintype "no_connect"))
    )
    (net (code "110") (name "unconnected-(U6-R232-Pad15)") (class "Default")
      (node (ref "U6") (pin "15") (pinfunction "R232_15") (pintype "bidirectional"))
    )
    (net (code "111") (name "unconnected-(U6-~{CTS}-Pad9)") (class "Default")
      (node (ref "U6") (pin "9") (pinfunction "~{CTS}_9") (pintype "bidirectional"))
    )
    (net (code "112") (name "unconnected-(U6-~{DCD}-Pad12)") (class "Default")
      (node (ref "U6") (pin "12") (pinfunction "~{DCD}_12") (pintype "bidirectional"))
    )
    (net (code "113") (name "unconnected-(U6-~{DSR}-Pad10)") (class "Default")
      (node (ref "U6") (pin "10") (pinfunction "~{DSR}_10") (pintype "bidirectional"))
    )
    (net (code "114") (name "unconnected-(U6-~{RI}-Pad11)") (class "Default")
      (node (ref "U6") (pin "11") (pinfunction "~{RI}_11") (pintype "bidirectional"))
    )
    (net (code "115") (name "unconnected-(U10-STAT2-Pad4)") (class "Default")
      (node (ref "U10") (pin "4") (pinfunction "STAT2_4") (pintype "bidirectional"))
    )
    (net (code "116") (name "unconnected-(U10-~{PG}-Pad7)") (class "Default")
      (node (ref "U10") (pin "7") (pinfunction "~{PG}_7") (pintype "bidirectional"))
    )
  )
)
